# CarrierConnector.net
KiCad netlist of a schematic drawn in Altium Designer
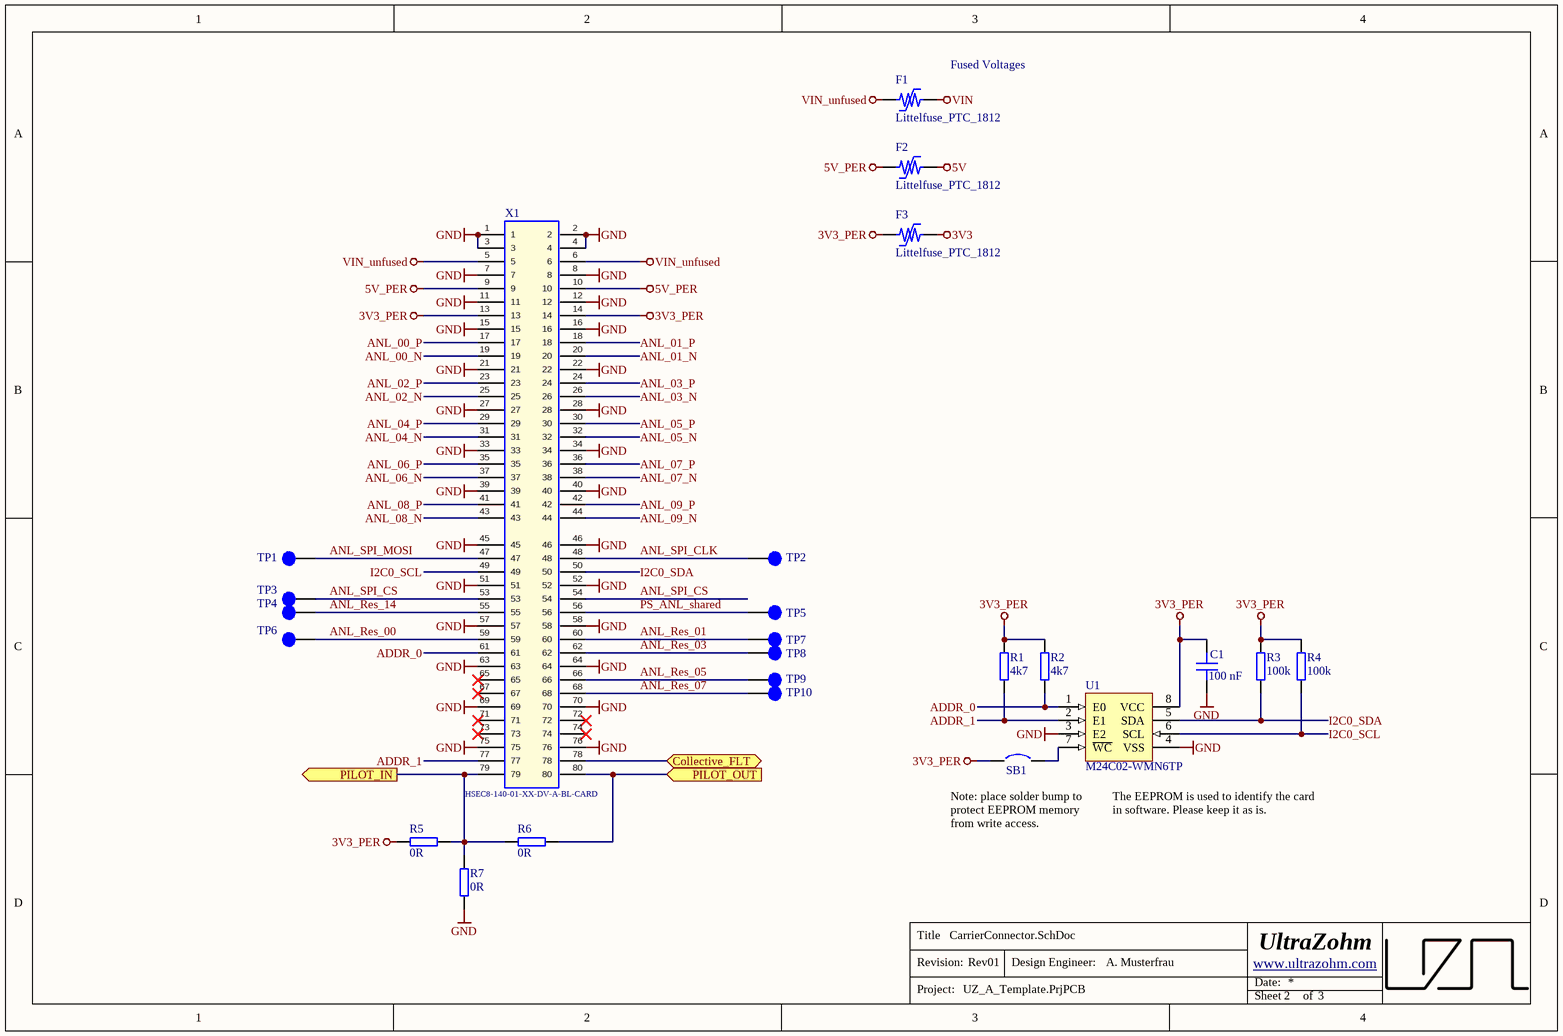
[diagram p0: CarrierConnector.SchDoc]

(export (version "E")
  (design (tool "Eeschema 10.0.6"))
  (components
    (comp (ref "C1")
      (value "100 nF")
      (footprint "C_0603")
      (description "Capacitor 0603, 6.3 VDC, 100 nF, X5R")
      (fields
        (field (name "MANUFACTURER PART NUMBER") "C0603C104K9PACTU")
        (field (name "MANUFACTURER") "KEMET")
        (field (name "CREATED FROM") "MGremer")
      )
      (libsource (lib "user") (part "Capacitor"))
    )
    (comp (ref "F1")
      (value "Littelfuse_PTC_1812")
      (footprint "1812_PTC_Polyfuse_Littelfuse")
      (description "POLYSWITCH RESETTABLE DEVICES")
      (fields
        (field (name "MPN") "miniASMDC110F/24")
        (field (name "MF") "Littelfuse")
        (field (name "CREATED") "2019_02_10_AGeiger")
        (field (name "CREATED FROM") "MHlatky")
      )
      (libsource (lib "user") (part "Littelfuse_PTC_1812"))
    )
    (comp (ref "F2")
      (value "Littelfuse_PTC_1812")
      (footprint "1812_PTC_Polyfuse_Littelfuse")
      (description "POLYSWITCH RESETTABLE DEVICES")
      (fields
        (field (name "MPN") "miniASMDC110F/24")
        (field (name "MF") "Littelfuse")
        (field (name "CREATED") "2019_02_10_AGeiger")
        (field (name "CREATED FROM") "MHlatky")
      )
      (libsource (lib "user") (part "Littelfuse_PTC_1812"))
    )
    (comp (ref "F3")
      (value "Littelfuse_PTC_1812")
      (footprint "1812_PTC_Polyfuse_Littelfuse")
      (description "POLYSWITCH RESETTABLE DEVICES")
      (fields
        (field (name "MPN") "miniASMDC110F/24")
        (field (name "MF") "Littelfuse")
        (field (name "CREATED") "2019_02_10_AGeiger")
        (field (name "CREATED FROM") "MHlatky")
      )
      (libsource (lib "user") (part "Littelfuse_PTC_1812"))
    )
    (comp (ref "R1")
      (value "4k7")
      (footprint "RES 0603_1608")
      (description "SMD resistor E24 series")
      (fields
        (field (name "MANUFACTURER PART NUMBER") "0603WAF4701T5E")
        (field (name "MANUFACTURER") "UNI-ROYAL")
        (field (name "CREATED FROM") "AGeiger")
      )
      (libsource (lib "user") (part "Resistor"))
    )
    (comp (ref "R2")
      (value "4k7")
      (footprint "RES 0603_1608")
      (description "SMD resistor E24 series")
      (fields
        (field (name "MANUFACTURER PART NUMBER") "0603WAF4701T5E")
        (field (name "MANUFACTURER") "UNI-ROYAL")
        (field (name "CREATED FROM") "AGeiger")
      )
      (libsource (lib "user") (part "Resistor"))
    )
    (comp (ref "R3")
      (value "100k")
      (footprint "RES 0603_1608")
      (description "SMD resistor E24 series")
      (fields
        (field (name "MANUFACTURER PART NUMBER") "RK73B1JTTD104J")
        (field (name "MANUFACTURER") "KOA Speer")
        (field (name "CREATED FROM") "MGremer")
      )
      (libsource (lib "user") (part "Resistor"))
    )
    (comp (ref "R4")
      (value "100k")
      (footprint "RES 0603_1608")
      (description "SMD resistor E24 series")
      (fields
        (field (name "MANUFACTURER PART NUMBER") "RK73B1JTTD104J")
        (field (name "MANUFACTURER") "KOA Speer")
        (field (name "CREATED FROM") "MGremer")
      )
      (libsource (lib "user") (part "Resistor"))
    )
    (comp (ref "R5")
      (value "0R")
      (footprint "RES 0603_1608")
      (description "SMD resistor E24 series")
      (fields
        (field (name "MANUFACTURER PART NUMBER") "RC0603JR-070RL")
        (field (name "MANUFACTURER") "YAGEO")
        (field (name "CREATED FROM") "MGremer")
      )
      (libsource (lib "user") (part "Resistor"))
    )
    (comp (ref "R6")
      (value "0R")
      (footprint "RES 0603_1608")
      (description "SMD resistor E24 series")
      (fields
        (field (name "MANUFACTURER PART NUMBER") "RC0603JR-070RL")
        (field (name "MANUFACTURER") "YAGEO")
        (field (name "CREATED FROM") "MGremer")
      )
      (libsource (lib "user") (part "Resistor"))
    )
    (comp (ref "R7")
      (value "0R")
      (footprint "RES 0603_1608")
      (description "SMD resistor E24 series")
      (fields
        (field (name "MANUFACTURER PART NUMBER") "RC0603JR-070RL")
        (field (name "MANUFACTURER") "YAGEO")
        (field (name "CREATED FROM") "MGremer")
      )
      (libsource (lib "user") (part "Resistor"))
    )
    (comp (ref "SB1")
      (value "Solder Bump 0603")
      (footprint "SB_0603")
      (fields (field (name "CREATED FROM") "AGeiger"))
      (libsource (lib "user") (part "Solder_Bump"))
    )
    (comp (ref "TP1")
      (value "PIN47")
      (footprint "TP_1mm")
      (description "Testpoint 1mm")
      (fields (field (name "CREATED") "2018_06_25_AGeiger"))
      (libsource (lib "UltraZOhm_CarrierBoard") (part "TP_1mm"))
    )
    (comp (ref "TP2")
      (value "PIN48")
      (footprint "TP_1mm")
      (description "Testpoint 1mm")
      (fields (field (name "CREATED") "2018_06_25_AGeiger"))
      (libsource (lib "UltraZOhm_CarrierBoard") (part "TP_1mm"))
    )
    (comp (ref "TP3")
      (value "PIN53")
      (footprint "TP_1mm")
      (description "Testpoint 1mm")
      (fields (field (name "CREATED") "2018_06_25_AGeiger"))
      (libsource (lib "UltraZOhm_CarrierBoard") (part "TP_1mm"))
    )
    (comp (ref "TP4")
      (value "PIN53")
      (footprint "TP_1mm")
      (description "Testpoint 1mm")
      (fields (field (name "CREATED") "2018_06_25_AGeiger"))
      (libsource (lib "UltraZOhm_CarrierBoard") (part "TP_1mm"))
    )
    (comp (ref "TP5")
      (value "PIN56")
      (footprint "TP_1mm")
      (description "Testpoint 1mm")
      (fields (field (name "CREATED") "2018_06_25_AGeiger"))
      (libsource (lib "UltraZOhm_CarrierBoard") (part "TP_1mm"))
    )
    (comp (ref "TP6")
      (value "PIN53")
      (footprint "TP_1mm")
      (description "Testpoint 1mm")
      (fields (field (name "CREATED") "2018_06_25_AGeiger"))
      (libsource (lib "UltraZOhm_CarrierBoard") (part "TP_1mm"))
    )
    (comp (ref "TP7")
      (value "PIN53")
      (footprint "TP_1mm")
      (description "Testpoint 1mm")
      (fields (field (name "CREATED") "2018_06_25_AGeiger"))
      (libsource (lib "UltraZOhm_CarrierBoard") (part "TP_1mm"))
    )
    (comp (ref "TP8")
      (value "PIN53")
      (footprint "TP_1mm")
      (description "Testpoint 1mm")
      (fields (field (name "CREATED") "2018_06_25_AGeiger"))
      (libsource (lib "UltraZOhm_CarrierBoard") (part "TP_1mm"))
    )
    (comp (ref "TP9")
      (value "PIN53")
      (footprint "TP_1mm")
      (description "Testpoint 1mm")
      (fields (field (name "CREATED") "2018_06_25_AGeiger"))
      (libsource (lib "UltraZOhm_CarrierBoard") (part "TP_1mm"))
    )
    (comp (ref "TP10")
      (value "PIN53")
      (footprint "TP_1mm")
      (description "Testpoint 1mm")
      (fields (field (name "CREATED") "2018_06_25_AGeiger"))
      (libsource (lib "UltraZOhm_CarrierBoard") (part "TP_1mm"))
    )
    (comp (ref "U1")
      (value "M24C02-WMN6TP")
      (footprint "D0008A_N")
      (description "2Kbit I2C SOP-8 EEPROM ROHS")
      (fields
        (field (name "MANUFACTURER") "STMicroelectronics")
        (field (name "LCSC PART NUMBER") "C7562")
        (field (name "CREATED FROM") "AGeiger")
      )
      (libsource (lib "user") (part "M24256"))
    )
    (comp (ref "X1")
      (value "HSEC8-140-01-XX-DV-A-BL-CARD")
      (footprint "UZohmADC:HSEC8-140-01-XX-DV-A-BL-CARD")
      (description "Mating Card Layout for HSEC8-140-01-XX-DV-A-BL")
      (fields (field (name "MANUFACTURER") "SAMTEC") (field (name "CREATED") "2018_04_23_AGeiger"))
      (libsource (lib "UltraZohm_ADC") (part "HSEC8-140-01-XX-DV-A-BL-CARD"))
    )
  )
  (nets
    (net (code "1") (name "/ADDR_0") (class "Default")
      (node (ref "R2") (pin "1") (pinfunction "1_1") (pintype "passive"))
      (node (ref "U1") (pin "1") (pinfunction "E0_1") (pintype "input"))
      (node (ref "X1") (pin "61") (pinfunction "61_61") (pintype "passive"))
    )
    (net (code "2") (name "/ADDR_1") (class "Default")
      (node (ref "R1") (pin "1") (pinfunction "1_1") (pintype "passive"))
      (node (ref "U1") (pin "2") (pinfunction "E1_2") (pintype "input"))
      (node (ref "X1") (pin "77") (pinfunction "77_77") (pintype "passive"))
    )
    (net (code "3") (name "/ANL_00_N") (class "Default")
      (node (ref "X1") (pin "19") (pinfunction "19_19") (pintype "passive"))
    )
    (net (code "4") (name "/ANL_00_P") (class "Default")
      (node (ref "X1") (pin "17") (pinfunction "17_17") (pintype "passive"))
    )
    (net (code "5") (name "/ANL_01_N") (class "Default")
      (node (ref "X1") (pin "20") (pinfunction "20_20") (pintype "passive"))
    )
    (net (code "6") (name "/ANL_01_P") (class "Default")
      (node (ref "X1") (pin "18") (pinfunction "18_18") (pintype "passive"))
    )
    (net (code "7") (name "/ANL_02_N") (class "Default")
      (node (ref "X1") (pin "25") (pinfunction "25_25") (pintype "passive"))
    )
    (net (code "8") (name "/ANL_02_P") (class "Default")
      (node (ref "X1") (pin "23") (pinfunction "23_23") (pintype "passive"))
    )
    (net (code "9") (name "/ANL_03_N") (class "Default")
      (node (ref "X1") (pin "26") (pinfunction "26_26") (pintype "passive"))
    )
    (net (code "10") (name "/ANL_03_P") (class "Default")
      (node (ref "X1") (pin "24") (pinfunction "24_24") (pintype "passive"))
    )
    (net (code "11") (name "/ANL_04_N") (class "Default")
      (node (ref "X1") (pin "31") (pinfunction "31_31") (pintype "passive"))
    )
    (net (code "12") (name "/ANL_04_P") (class "Default")
      (node (ref "X1") (pin "29") (pinfunction "29_29") (pintype "passive"))
    )
    (net (code "13") (name "/ANL_05_N") (class "Default")
      (node (ref "X1") (pin "32") (pinfunction "32_32") (pintype "passive"))
    )
    (net (code "14") (name "/ANL_05_P") (class "Default")
      (node (ref "X1") (pin "30") (pinfunction "30_30") (pintype "passive"))
    )
    (net (code "15") (name "/ANL_06_N") (class "Default")
      (node (ref "X1") (pin "37") (pinfunction "37_37") (pintype "passive"))
    )
    (net (code "16") (name "/ANL_06_P") (class "Default")
      (node (ref "X1") (pin "35") (pinfunction "35_35") (pintype "passive"))
    )
    (net (code "17") (name "/ANL_07_N") (class "Default")
      (node (ref "X1") (pin "38") (pinfunction "38_38") (pintype "passive"))
    )
    (net (code "18") (name "/ANL_07_P") (class "Default")
      (node (ref "X1") (pin "36") (pinfunction "36_36") (pintype "passive"))
    )
    (net (code "19") (name "/ANL_08_N") (class "Default")
      (node (ref "X1") (pin "43") (pinfunction "43_43") (pintype "passive"))
    )
    (net (code "20") (name "/ANL_08_P") (class "Default")
      (node (ref "X1") (pin "41") (pinfunction "41_41") (pintype "passive"))
    )
    (net (code "21") (name "/ANL_09_N") (class "Default")
      (node (ref "X1") (pin "44") (pinfunction "44_44") (pintype "passive"))
    )
    (net (code "22") (name "/ANL_09_P") (class "Default")
      (node (ref "X1") (pin "42") (pinfunction "42_42") (pintype "passive"))
    )
    (net (code "23") (name "/ANL_Res_00") (class "Default")
      (node (ref "TP6") (pin "1") (pintype "passive"))
      (node (ref "X1") (pin "59") (pinfunction "59_59") (pintype "passive"))
    )
    (net (code "24") (name "/ANL_Res_01") (class "Default")
      (node (ref "TP7") (pin "1") (pintype "passive"))
      (node (ref "X1") (pin "60") (pinfunction "60_60") (pintype "passive"))
    )
    (net (code "25") (name "/ANL_Res_03") (class "Default")
      (node (ref "TP8") (pin "1") (pintype "passive"))
      (node (ref "X1") (pin "62") (pinfunction "62_62") (pintype "passive"))
    )
    (net (code "26") (name "/ANL_Res_05") (class "Default")
      (node (ref "TP9") (pin "1") (pintype "passive"))
      (node (ref "X1") (pin "66") (pinfunction "66_66") (pintype "passive"))
    )
    (net (code "27") (name "/ANL_Res_07") (class "Default")
      (node (ref "TP10") (pin "1") (pintype "passive"))
      (node (ref "X1") (pin "68") (pinfunction "68_68") (pintype "passive"))
    )
    (net (code "28") (name "/ANL_Res_14") (class "Default")
      (node (ref "TP4") (pin "1") (pintype "passive"))
      (node (ref "X1") (pin "55") (pinfunction "55_55") (pintype "passive"))
    )
    (net (code "29") (name "/ANL_SPI_CLK") (class "Default")
      (node (ref "TP2") (pin "1") (pintype "passive"))
      (node (ref "X1") (pin "48") (pinfunction "48_48") (pintype "passive"))
    )
    (net (code "30") (name "/ANL_SPI_CS") (class "Default")
      (node (ref "TP3") (pin "1") (pintype "passive"))
      (node (ref "X1") (pin "53") (pinfunction "53_53") (pintype "passive"))
      (node (ref "X1") (pin "54") (pinfunction "54_54") (pintype "passive"))
    )
    (net (code "31") (name "/ANL_SPI_MOSI") (class "Default")
      (node (ref "TP1") (pin "1") (pintype "passive"))
      (node (ref "X1") (pin "47") (pinfunction "47_47") (pintype "passive"))
    )
    (net (code "32") (name "/Collective_FLT") (class "Default")
      (node (ref "X1") (pin "78") (pinfunction "78_78") (pintype "passive"))
    )
    (net (code "33") (name "/I2C0_SCL") (class "Default")
      (node (ref "R4") (pin "1") (pinfunction "1_1") (pintype "passive"))
      (node (ref "U1") (pin "6") (pinfunction "SCL_6") (pintype "input"))
      (node (ref "X1") (pin "49") (pinfunction "49_49") (pintype "passive"))
    )
    (net (code "34") (name "/I2C0_SDA") (class "Default")
      (node (ref "R3") (pin "1") (pinfunction "1_1") (pintype "passive"))
      (node (ref "U1") (pin "5") (pinfunction "SDA_5") (pintype "open_collector"))
      (node (ref "X1") (pin "50") (pinfunction "50_50") (pintype "passive"))
    )
    (net (code "35") (name "/PILOT_IN") (class "Default")
      (node (ref "R5") (pin "2") (pinfunction "2_2") (pintype "passive"))
      (node (ref "R6") (pin "1") (pinfunction "1_1") (pintype "passive"))
      (node (ref "R7") (pin "2") (pinfunction "2_2") (pintype "passive"))
      (node (ref "X1") (pin "79") (pinfunction "79_79") (pintype "passive"))
    )
    (net (code "36") (name "/PILOT_OUT") (class "Default")
      (node (ref "R6") (pin "2") (pinfunction "2_2") (pintype "passive"))
      (node (ref "X1") (pin "80") (pinfunction "80_80") (pintype "passive"))
    )
    (net (code "37") (name "/PS_ANL_shared") (class "Default")
      (node (ref "TP5") (pin "1") (pintype "passive"))
      (node (ref "X1") (pin "56") (pinfunction "56_56") (pintype "passive"))
    )
    (net (code "38") (name "3V3") (class "Default")
      (node (ref "F3") (pin "2") (pinfunction "2_2") (pintype "passive"))
    )
    (net (code "39") (name "3V3_PER") (class "Default")
      (node (ref "C1") (pin "1") (pinfunction "1_1") (pintype "passive"))
      (node (ref "F3") (pin "1") (pinfunction "1_1") (pintype "passive"))
      (node (ref "R1") (pin "2") (pinfunction "2_2") (pintype "passive"))
      (node (ref "R2") (pin "2") (pinfunction "2_2") (pintype "passive"))
      (node (ref "R3") (pin "2") (pinfunction "2_2") (pintype "passive"))
      (node (ref "R4") (pin "2") (pinfunction "2_2") (pintype "passive"))
      (node (ref "R5") (pin "1") (pinfunction "1_1") (pintype "passive"))
      (node (ref "SB1") (pin "1") (pinfunction "1_1") (pintype "passive"))
      (node (ref "U1") (pin "8") (pinfunction "VCC_8") (pintype "power_in"))
      (node (ref "X1") (pin "13") (pinfunction "13_13") (pintype "passive"))
      (node (ref "X1") (pin "14") (pinfunction "14_14") (pintype "passive"))
    )
    (net (code "40") (name "5V") (class "Default")
      (node (ref "F2") (pin "2") (pinfunction "2_2") (pintype "passive"))
    )
    (net (code "41") (name "5V_PER") (class "Default")
      (node (ref "F2") (pin "1") (pinfunction "1_1") (pintype "passive"))
      (node (ref "X1") (pin "10") (pinfunction "10_10") (pintype "passive"))
      (node (ref "X1") (pin "9") (pinfunction "9_9") (pintype "passive"))
    )
    (net (code "42") (name "GND") (class "Default")
      (node (ref "C1") (pin "2") (pinfunction "2_2") (pintype "passive"))
      (node (ref "R7") (pin "1") (pinfunction "1_1") (pintype "passive"))
      (node (ref "U1") (pin "3") (pinfunction "E2_3") (pintype "input"))
      (node (ref "U1") (pin "4") (pinfunction "VSS_4") (pintype "power_in"))
      (node (ref "X1") (pin "1") (pinfunction "1_1") (pintype "passive"))
      (node (ref "X1") (pin "11") (pinfunction "11_11") (pintype "passive"))
      (node (ref "X1") (pin "12") (pinfunction "12_12") (pintype "passive"))
      (node (ref "X1") (pin "15") (pinfunction "15_15") (pintype "passive"))
      (node (ref "X1") (pin "16") (pinfunction "16_16") (pintype "passive"))
      (node (ref "X1") (pin "2") (pinfunction "2_2") (pintype "passive"))
      (node (ref "X1") (pin "21") (pinfunction "21_21") (pintype "passive"))
      (node (ref "X1") (pin "22") (pinfunction "22_22") (pintype "passive"))
      (node (ref "X1") (pin "27") (pinfunction "27_27") (pintype "passive"))
      (node (ref "X1") (pin "28") (pinfunction "28_28") (pintype "passive"))
      (node (ref "X1") (pin "3") (pinfunction "3_3") (pintype "passive"))
      (node (ref "X1") (pin "33") (pinfunction "33_33") (pintype "passive"))
      (node (ref "X1") (pin "34") (pinfunction "34_34") (pintype "passive"))
      (node (ref "X1") (pin "39") (pinfunction "39_39") (pintype "passive"))
      (node (ref "X1") (pin "4") (pinfunction "4_4") (pintype "passive"))
      (node (ref "X1") (pin "40") (pinfunction "40_40") (pintype "passive"))
      (node (ref "X1") (pin "45") (pinfunction "45_45") (pintype "passive"))
      (node (ref "X1") (pin "46") (pinfunction "46_46") (pintype "passive"))
      (node (ref "X1") (pin "51") (pinfunction "51_51") (pintype "passive"))
      (node (ref "X1") (pin "52") (pinfunction "52_52") (pintype "passive"))
      (node (ref "X1") (pin "57") (pinfunction "57_57") (pintype "passive"))
      (node (ref "X1") (pin "58") (pinfunction "58_58") (pintype "passive"))
      (node (ref "X1") (pin "63") (pinfunction "63_63") (pintype "passive"))
      (node (ref "X1") (pin "64") (pinfunction "64_64") (pintype "passive"))
      (node (ref "X1") (pin "69") (pinfunction "69_69") (pintype "passive"))
      (node (ref "X1") (pin "7") (pinfunction "7_7") (pintype "passive"))
      (node (ref "X1") (pin "70") (pinfunction "70_70") (pintype "passive"))
      (node (ref "X1") (pin "75") (pinfunction "75_75") (pintype "passive"))
      (node (ref "X1") (pin "76") (pinfunction "76_76") (pintype "passive"))
      (node (ref "X1") (pin "8") (pinfunction "8_8") (pintype "passive"))
    )
    (net (code "43") (name "Net-(U1-~{WC})") (class "Default")
      (node (ref "SB1") (pin "2") (pinfunction "2_2") (pintype "passive"))
      (node (ref "U1") (pin "7") (pinfunction "~{WC}_7") (pintype "input"))
    )
    (net (code "44") (name "VIN") (class "Default")
      (node (ref "F1") (pin "2") (pinfunction "2_2") (pintype "passive"))
    )
    (net (code "45") (name "VIN_unfused") (class "Default")
      (node (ref "F1") (pin "1") (pinfunction "1_1") (pintype "passive"))
      (node (ref "X1") (pin "5") (pinfunction "5_5") (pintype "passive"))
      (node (ref "X1") (pin "6") (pinfunction "6_6") (pintype "passive"))
    )
    (net (code "46") (name "unconnected-(X1-Pad65)") (class "Default")
      (node (ref "X1") (pin "65") (pinfunction "65_65") (pintype "passive+no_connect"))
    )
    (net (code "47") (name "unconnected-(X1-Pad67)") (class "Default")
      (node (ref "X1") (pin "67") (pinfunction "67_67") (pintype "passive+no_connect"))
    )
    (net (code "48") (name "unconnected-(X1-Pad71)") (class "Default")
      (node (ref "X1") (pin "71") (pinfunction "71_71") (pintype "passive+no_connect"))
    )
    (net (code "49") (name "unconnected-(X1-Pad72)") (class "Default")
      (node (ref "X1") (pin "72") (pinfunction "72_72") (pintype "passive+no_connect"))
    )
    (net (code "50") (name "unconnected-(X1-Pad73)") (class "Default")
      (node (ref "X1") (pin "73") (pinfunction "73_73") (pintype "passive+no_connect"))
    )
    (net (code "51") (name "unconnected-(X1-Pad74)") (class "Default")
      (node (ref "X1") (pin "74") (pinfunction "74_74") (pintype "passive+no_connect"))
    )
  )
)
